# LM_001.net
KiCad netlist of a schematic drawn in Altium Designer
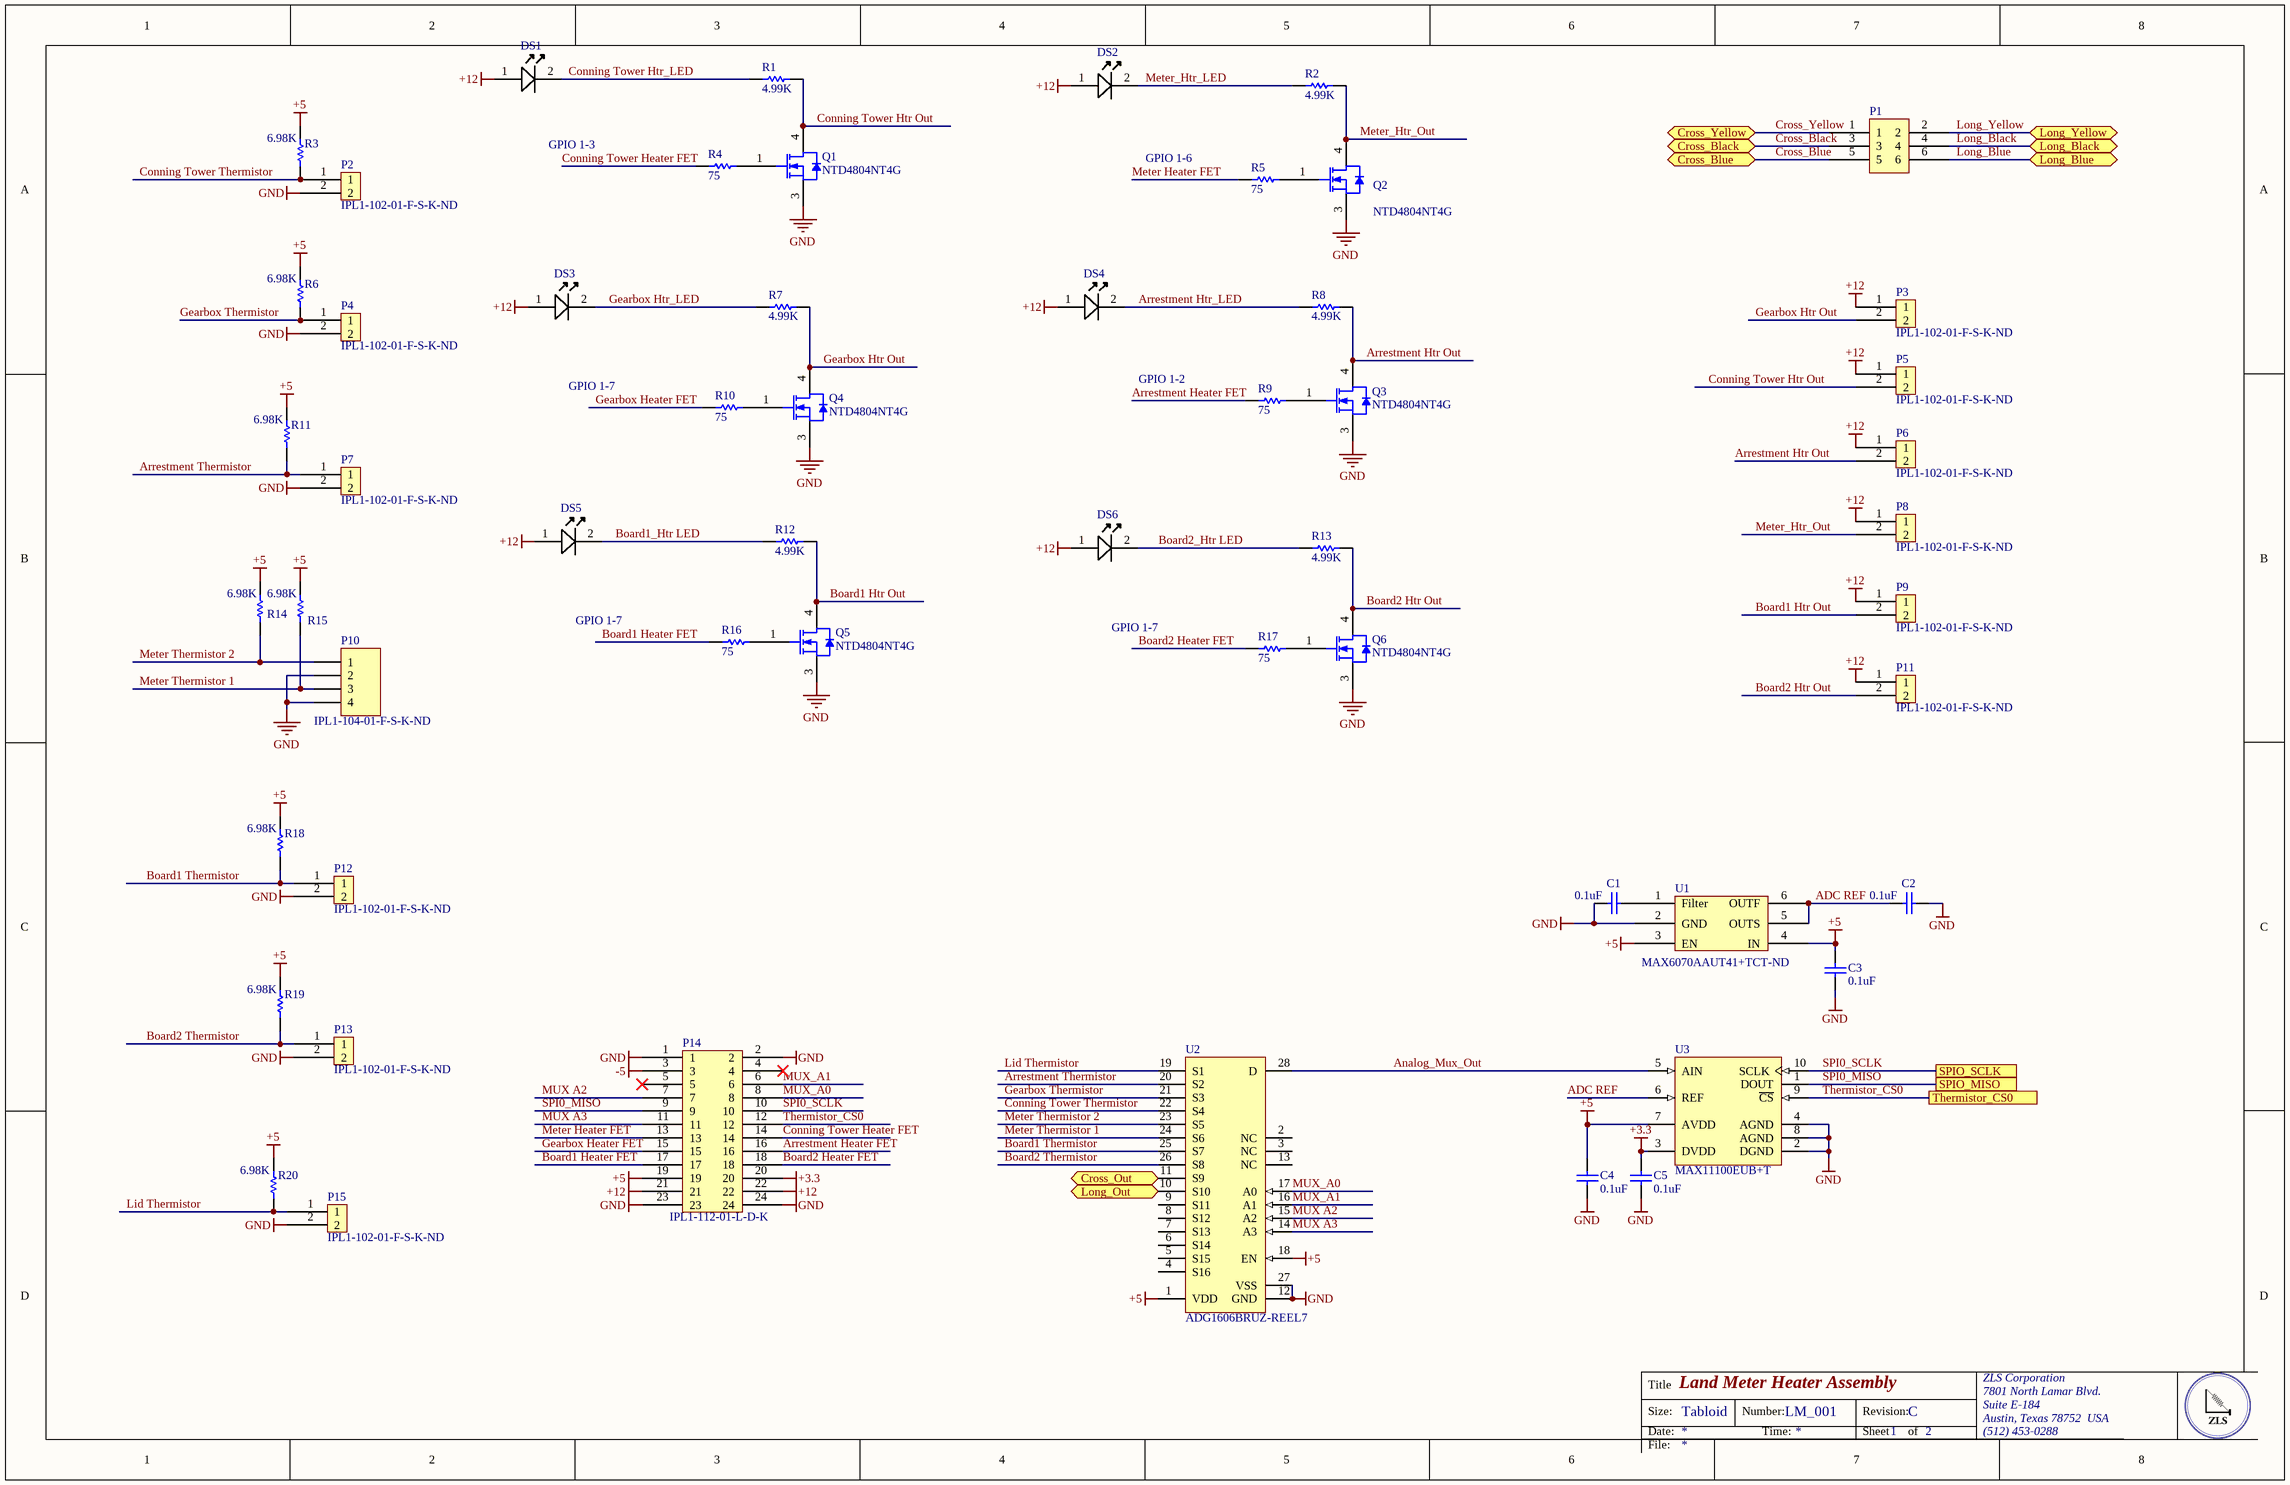
[diagram p0: LM_001.SchDoc]

(export (version "E")
  (design (tool "Eeschema 10.0.6"))
  (components
    (comp (ref "C1")
      (value "0.1uF")
      (footprint "CAPC0402(1005)60_L")
      (description "CAP CER 0.1UF 10V X7R 0402")
      (fields
        (field (name "MANUFACTURER") "Murata Electronics North America")
        (field (name "MANUFACTURER PART NUMBER") "GRM155R71A104KA01D")
      )
      (libsource (lib "Altium Content Vault") (part "CMP-1034-00252-1"))
    )
    (comp (ref "C2")
      (value "0.1uF")
      (footprint "CAPC0402(1005)60_L")
      (description "CAP CER 0.1UF 10V X7R 0402")
      (fields
        (field (name "MANUFACTURER") "Murata Electronics North America")
        (field (name "MANUFACTURER PART NUMBER") "GRM155R71A104KA01D")
      )
      (libsource (lib "Altium Content Vault") (part "CMP-1034-00252-1"))
    )
    (comp (ref "C3")
      (value "0.1uF")
      (footprint "CAPC0402(1005)60_L")
      (description "CAP CER 0.1UF 10V X7R 0402")
      (fields
        (field (name "MANUFACTURER") "Murata Electronics North America")
        (field (name "MANUFACTURER PART NUMBER") "GRM155R71A104KA01D")
      )
      (libsource (lib "Altium Content Vault") (part "CMP-1034-00252-1"))
    )
    (comp (ref "C4")
      (value "0.1uF")
      (footprint "CAPC0402(1005)60_L")
      (description "CAP CER 0.1UF 10V X7R 0402")
      (fields
        (field (name "MANUFACTURER") "Murata Electronics North America")
        (field (name "MANUFACTURER PART NUMBER") "GRM155R71A104KA01D")
      )
      (libsource (lib "Altium Content Vault") (part "CMP-1034-00252-1"))
    )
    (comp (ref "C5")
      (value "0.1uF")
      (footprint "CAPC0402(1005)60_L")
      (description "CAP CER 0.1UF 10V X7R 0402")
      (fields
        (field (name "MANUFACTURER") "Murata Electronics North America")
        (field (name "MANUFACTURER PART NUMBER") "GRM155R71A104KA01D")
      )
      (libsource (lib "Altium Content Vault") (part "CMP-1034-00252-1"))
    )
    (comp (ref "DS1")
      (value "LTST-S220KRKT")
      (footprint "0805C_L")
      (description "LED RED CLEAR CHIP SMD R/A")
      (fields (field (name "MANUFACTURER") "Vishay / Lite-On"))
      (libsource (lib "*") (part "LED A/K"))
    )
    (comp (ref "DS2")
      (value "LTST-S220KRKT")
      (footprint "0805C_L")
      (description "LED RED CLEAR CHIP SMD R/A")
      (fields (field (name "MANUFACTURER") "Vishay / Lite-On"))
      (libsource (lib "*") (part "LED A/K"))
    )
    (comp (ref "DS3")
      (value "LTST-S220KRKT")
      (footprint "0805C_L")
      (description "LED RED CLEAR CHIP SMD R/A")
      (fields (field (name "MANUFACTURER") "Vishay / Lite-On"))
      (libsource (lib "*") (part "LED A/K"))
    )
    (comp (ref "DS4")
      (value "LTST-S220KRKT")
      (footprint "0805C_L")
      (description "LED RED CLEAR CHIP SMD R/A")
      (fields (field (name "MANUFACTURER") "Vishay / Lite-On"))
      (libsource (lib "*") (part "LED A/K"))
    )
    (comp (ref "DS5")
      (value "LTST-S220KRKT")
      (footprint "0805C_L")
      (description "LED RED CLEAR CHIP SMD R/A")
      (fields (field (name "MANUFACTURER") "Vishay / Lite-On"))
      (libsource (lib "*") (part "LED A/K"))
    )
    (comp (ref "DS6")
      (value "LTST-S220KRKT")
      (footprint "0805C_L")
      (description "LED RED CLEAR CHIP SMD R/A")
      (fields (field (name "MANUFACTURER") "Vishay / Lite-On"))
      (libsource (lib "*") (part "LED A/K"))
    )
    (comp (ref "P1")
      (value "IPL1-103-01-L-D-K")
      (footprint "IPL1-103-01-F-D")
      (description ".100 TERMINAL ASSY")
      (fields (field (name "MANUFACTURER") "Samtec Inc."))
      (libsource (lib "ZLS_Schematic_lib") (part "IPL1-103-01-F-D"))
    )
    (comp (ref "P2")
      (value "IPL1-102-01-F-S-K")
      (footprint "IPL1-102-01-F-S-K")
      (description ".100 TERMINAL ASSEMBLY")
      (fields
        (field (name "SUPPLIER PART NUMBER 1") "IPL1-102-01-F-S-K-ND")
        (field (name "MANUFACTURER") "Samtec Inc.")
      )
      (libsource (lib "ZLS_Schematic_lib") (part "IPL1-102-01-F-S-K"))
    )
    (comp (ref "P3")
      (value "IPL1-102-01-F-S-K")
      (footprint "IPL1-102-01-F-S-K")
      (description ".100 TERMINAL ASSEMBLY")
      (fields
        (field (name "SUPPLIER PART NUMBER 1") "IPL1-102-01-F-S-K-ND")
        (field (name "MANUFACTURER") "Samtec Inc.")
      )
      (libsource (lib "ZLS_Schematic_lib") (part "IPL1-102-01-F-S-K"))
    )
    (comp (ref "P4")
      (value "IPL1-102-01-F-S-K")
      (footprint "IPL1-102-01-F-S-K")
      (description ".100 TERMINAL ASSEMBLY")
      (fields
        (field (name "SUPPLIER PART NUMBER 1") "IPL1-102-01-F-S-K-ND")
        (field (name "MANUFACTURER") "Samtec Inc.")
      )
      (libsource (lib "ZLS_Schematic_lib") (part "IPL1-102-01-F-S-K"))
    )
    (comp (ref "P5")
      (value "IPL1-102-01-F-S-K")
      (footprint "IPL1-102-01-F-S-K")
      (description ".100 TERMINAL ASSEMBLY")
      (fields
        (field (name "SUPPLIER PART NUMBER 1") "IPL1-102-01-F-S-K-ND")
        (field (name "MANUFACTURER") "Samtec Inc.")
      )
      (libsource (lib "ZLS_Schematic_lib") (part "IPL1-102-01-F-S-K"))
    )
    (comp (ref "P6")
      (value "IPL1-102-01-F-S-K")
      (footprint "IPL1-102-01-F-S-K")
      (description ".100 TERMINAL ASSEMBLY")
      (fields
        (field (name "SUPPLIER PART NUMBER 1") "IPL1-102-01-F-S-K-ND")
        (field (name "MANUFACTURER") "Samtec Inc.")
      )
      (libsource (lib "ZLS_Schematic_lib") (part "IPL1-102-01-F-S-K"))
    )
    (comp (ref "P7")
      (value "IPL1-102-01-F-S-K")
      (footprint "IPL1-102-01-F-S-K")
      (description ".100 TERMINAL ASSEMBLY")
      (fields
        (field (name "SUPPLIER PART NUMBER 1") "IPL1-102-01-F-S-K-ND")
        (field (name "MANUFACTURER") "Samtec Inc.")
      )
      (libsource (lib "ZLS_Schematic_lib") (part "IPL1-102-01-F-S-K"))
    )
    (comp (ref "P8")
      (value "IPL1-102-01-F-S-K")
      (footprint "IPL1-102-01-F-S-K")
      (description ".100 TERMINAL ASSEMBLY")
      (fields
        (field (name "SUPPLIER PART NUMBER 1") "IPL1-102-01-F-S-K-ND")
        (field (name "MANUFACTURER") "Samtec Inc.")
      )
      (libsource (lib "ZLS_Schematic_lib") (part "IPL1-102-01-F-S-K"))
    )
    (comp (ref "P9")
      (value "IPL1-102-01-F-S-K")
      (footprint "IPL1-102-01-F-S-K")
      (description ".100 TERMINAL ASSEMBLY")
      (fields
        (field (name "SUPPLIER PART NUMBER 1") "IPL1-102-01-F-S-K-ND")
        (field (name "MANUFACTURER") "Samtec Inc.")
      )
      (libsource (lib "ZLS_Schematic_lib") (part "IPL1-102-01-F-S-K"))
    )
    (comp (ref "P10")
      (value "IPL1-104-01-F-S-K-ND")
      (footprint "IPL1-104-01-L-S-K")
      (description ".100 TERMINAL ASSEMBLY")
      (fields
        (field (name "MANUFACTURER") "Samtec Inc.")
        (field (name "MANUFACTURER PART NUMBER") "IPL1-104-01-F-S-K")
      )
      (libsource (lib "Miscellaneous Connectors") (part "Header 4"))
    )
    (comp (ref "P11")
      (value "IPL1-102-01-F-S-K")
      (footprint "IPL1-102-01-F-S-K")
      (description ".100 TERMINAL ASSEMBLY")
      (fields
        (field (name "SUPPLIER PART NUMBER 1") "IPL1-102-01-F-S-K-ND")
        (field (name "MANUFACTURER") "Samtec Inc.")
      )
      (libsource (lib "ZLS_Schematic_lib") (part "IPL1-102-01-F-S-K"))
    )
    (comp (ref "P12")
      (value "IPL1-102-01-F-S-K")
      (footprint "IPL1-102-01-F-S-K")
      (description ".100 TERMINAL ASSEMBLY")
      (fields
        (field (name "SUPPLIER PART NUMBER 1") "IPL1-102-01-F-S-K-ND")
        (field (name "MANUFACTURER") "Samtec Inc.")
      )
      (libsource (lib "ZLS_Schematic_lib") (part "IPL1-102-01-F-S-K"))
    )
    (comp (ref "P13")
      (value "IPL1-102-01-F-S-K")
      (footprint "IPL1-102-01-F-S-K")
      (description ".100 TERMINAL ASSEMBLY")
      (fields
        (field (name "SUPPLIER PART NUMBER 1") "IPL1-102-01-F-S-K-ND")
        (field (name "MANUFACTURER") "Samtec Inc.")
      )
      (libsource (lib "ZLS_Schematic_lib") (part "IPL1-102-01-F-S-K"))
    )
    (comp (ref "P14")
      (value "IPL1-112-01-L-D-K")
      (footprint "IPL1-112-01-F-S-K")
      (description ".100 TERMINAL ASSEMBLY")
      (fields (field (name "MANUFACTURER") "Samtec Inc."))
      (libsource (lib "ZLS_Schematic_lib") (part "IPL1-112-01-F-S-K"))
    )
    (comp (ref "P15")
      (value "IPL1-102-01-F-S-K")
      (footprint "IPL1-102-01-F-S-K")
      (description ".100 TERMINAL ASSEMBLY")
      (fields
        (field (name "SUPPLIER PART NUMBER 1") "IPL1-102-01-F-S-K-ND")
        (field (name "MANUFACTURER") "Samtec Inc.")
      )
      (libsource (lib "ZLS_Schematic_lib") (part "IPL1-102-01-F-S-K"))
    )
    (comp (ref "Q1")
      (value "NTD4804NT4G")
      (footprint "ONSC-DPAK-3-369AA-01_V")
      (description "Power MOSFET, 30 V, 117 A, Single N-Channel, 3-Pin DPAK, Pb-Free, Tape and Reel")
      (fields (field (name "MANUFACTURER") "On Semiconductor"))
      (libsource (lib "Altium Content Vault") (part "CMP-1058-00341-1"))
    )
    (comp (ref "Q2")
      (value "NTD4804NT4G")
      (footprint "ONSC-DPAK-3-369AA-01_V")
      (description "Power MOSFET, 30 V, 117 A, Single N-Channel, 3-Pin DPAK, Pb-Free, Tape and Reel")
      (fields (field (name "MANUFACTURER") "On Semiconductor"))
      (libsource (lib "Altium Content Vault") (part "CMP-1058-00341-1"))
    )
    (comp (ref "Q3")
      (value "NTD4804NT4G")
      (footprint "ONSC-DPAK-3-369AA-01_V")
      (description "Power MOSFET, 30 V, 117 A, Single N-Channel, 3-Pin DPAK, Pb-Free, Tape and Reel")
      (fields (field (name "MANUFACTURER") "On Semiconductor"))
      (libsource (lib "Altium Content Vault") (part "CMP-1058-00341-1"))
    )
    (comp (ref "Q4")
      (value "NTD4804NT4G")
      (footprint "ONSC-DPAK-3-369AA-01_V")
      (description "Power MOSFET, 30 V, 117 A, Single N-Channel, 3-Pin DPAK, Pb-Free, Tape and Reel")
      (fields (field (name "MANUFACTURER") "On Semiconductor"))
      (libsource (lib "Altium Content Vault") (part "CMP-1058-00341-1"))
    )
    (comp (ref "Q5")
      (value "NTD4804NT4G")
      (footprint "ONSC-DPAK-3-369AA-01_V")
      (description "Power MOSFET, 30 V, 117 A, Single N-Channel, 3-Pin DPAK, Pb-Free, Tape and Reel")
      (fields (field (name "MANUFACTURER") "On Semiconductor"))
      (libsource (lib "Altium Content Vault") (part "CMP-1058-00341-1"))
    )
    (comp (ref "Q6")
      (value "NTD4804NT4G")
      (footprint "ONSC-DPAK-3-369AA-01_V")
      (description "Power MOSFET, 30 V, 117 A, Single N-Channel, 3-Pin DPAK, Pb-Free, Tape and Reel")
      (fields (field (name "MANUFACTURER") "On Semiconductor"))
      (libsource (lib "Altium Content Vault") (part "CMP-1058-00341-1"))
    )
    (comp (ref "R1")
      (value "4.99K")
      (footprint "RESC0805(2012)_L")
      (description "RES SMD 4.99K OHM 1% 1/8W 0805")
      (fields
        (field (name "MANUFACTURER") "Vishay Dale")
        (field (name "MANUFACTURER PART NUMBER") "CRCW08054K99FKEA")
      )
      (libsource (lib "Altium Content Vault") (part "CMP-1013-00393-1"))
    )
    (comp (ref "R2")
      (value "4.99K")
      (footprint "RESC0805(2012)_L")
      (description "RES SMD 4.99K OHM 1% 1/8W 0805")
      (fields
        (field (name "MANUFACTURER") "Vishay Dale")
        (field (name "MANUFACTURER PART NUMBER") "CRCW08054K99FKEA")
      )
      (libsource (lib "Altium Content Vault") (part "CMP-1013-00393-1"))
    )
    (comp (ref "R3")
      (value "6.98K")
      (footprint "RESC0805(2012)_N")
      (description "RES SMD 6.98K OHM 1% 1/8W 0805")
      (fields
        (field (name "MANUFACTURER") "Vishay Dale")
        (field (name "MANUFACTURER PART NUMBER") "CRCW08056K98FKEA")
      )
      (libsource (lib "Altium Content Vault") (part "CMP-1013-00606-1"))
    )
    (comp (ref "R4")
      (value "75")
      (footprint "RESC0805(2012)_L")
      (description "RES SMD 75 OHM 1% 1/8W 0805")
      (fields
        (field (name "MANUFACTURER") "Vishay Dale")
        (field (name "MANUFACTURER PART NUMBER") "CRCW080575R0FKTA")
      )
      (libsource (lib "Altium Content Vault") (part "CMP-1013-00393-1"))
    )
    (comp (ref "R5")
      (value "75")
      (footprint "RESC0805(2012)_L")
      (description "RES SMD 75 OHM 1% 1/8W 0805")
      (fields
        (field (name "MANUFACTURER") "Vishay Dale")
        (field (name "MANUFACTURER PART NUMBER") "CRCW080575R0FKTA")
      )
      (libsource (lib "Altium Content Vault") (part "CMP-1013-00393-1"))
    )
    (comp (ref "R6")
      (value "6.98K")
      (footprint "RESC0805(2012)_N")
      (description "RES SMD 6.98K OHM 1% 1/8W 0805")
      (fields
        (field (name "MANUFACTURER") "Vishay Dale")
        (field (name "MANUFACTURER PART NUMBER") "CRCW08056K98FKEA")
      )
      (libsource (lib "Altium Content Vault") (part "CMP-1013-00606-1"))
    )
    (comp (ref "R7")
      (value "4.99K")
      (footprint "RESC0805(2012)_L")
      (description "RES SMD 4.99K OHM 1% 1/8W 0805")
      (fields
        (field (name "MANUFACTURER") "Vishay Dale")
        (field (name "MANUFACTURER PART NUMBER") "CRCW08054K99FKEA")
      )
      (libsource (lib "Altium Content Vault") (part "CMP-1013-00393-1"))
    )
    (comp (ref "R8")
      (value "4.99K")
      (footprint "RESC0805(2012)_L")
      (description "RES SMD 4.99K OHM 1% 1/8W 0805")
      (fields
        (field (name "MANUFACTURER") "Vishay Dale")
        (field (name "MANUFACTURER PART NUMBER") "CRCW08054K99FKEA")
      )
      (libsource (lib "Altium Content Vault") (part "CMP-1013-00393-1"))
    )
    (comp (ref "R9")
      (value "75")
      (footprint "RESC0805(2012)_L")
      (description "RES SMD 75 OHM 1% 1/8W 0805")
      (fields
        (field (name "MANUFACTURER") "Vishay Dale")
        (field (name "MANUFACTURER PART NUMBER") "CRCW080575R0FKTA")
      )
      (libsource (lib "Altium Content Vault") (part "CMP-1013-00393-1"))
    )
    (comp (ref "R10")
      (value "75")
      (footprint "RESC0805(2012)_L")
      (description "RES SMD 75 OHM 1% 1/8W 0805")
      (fields
        (field (name "MANUFACTURER") "Vishay Dale")
        (field (name "MANUFACTURER PART NUMBER") "CRCW080575R0FKTA")
      )
      (libsource (lib "Altium Content Vault") (part "CMP-1013-00393-1"))
    )
    (comp (ref "R11")
      (value "6.98K")
      (footprint "RESC0805(2012)_N")
      (description "RES SMD 6.98K OHM 1% 1/8W 0805")
      (fields
        (field (name "MANUFACTURER") "Vishay Dale")
        (field (name "MANUFACTURER PART NUMBER") "CRCW08056K98FKEA")
      )
      (libsource (lib "Altium Content Vault") (part "CMP-1013-00606-1"))
    )
    (comp (ref "R12")
      (value "4.99K")
      (footprint "RESC0805(2012)_L")
      (description "RES SMD 4.99K OHM 1% 1/8W 0805")
      (fields
        (field (name "MANUFACTURER") "Vishay Dale")
        (field (name "MANUFACTURER PART NUMBER") "CRCW08054K99FKEA")
      )
      (libsource (lib "Altium Content Vault") (part "CMP-1013-00393-1"))
    )
    (comp (ref "R13")
      (value "4.99K")
      (footprint "RESC0805(2012)_L")
      (description "RES SMD 4.99K OHM 1% 1/8W 0805")
      (fields
        (field (name "MANUFACTURER") "Vishay Dale")
        (field (name "MANUFACTURER PART NUMBER") "CRCW08054K99FKEA")
      )
      (libsource (lib "Altium Content Vault") (part "CMP-1013-00393-1"))
    )
    (comp (ref "R14")
      (value "6.98K")
      (footprint "RESC0805(2012)_N")
      (description "RES SMD 6.98K OHM 1% 1/8W 0805")
      (fields
        (field (name "MANUFACTURER") "Vishay Dale")
        (field (name "MANUFACTURER PART NUMBER") "CRCW08056K98FKEA")
      )
      (libsource (lib "Altium Content Vault") (part "CMP-1013-00606-1"))
    )
    (comp (ref "R15")
      (value "6.98K")
      (footprint "RESC0805(2012)_N")
      (description "RES SMD 6.98K OHM 1% 1/8W 0805")
      (fields
        (field (name "MANUFACTURER") "Vishay Dale")
        (field (name "MANUFACTURER PART NUMBER") "CRCW08056K98FKEA")
      )
      (libsource (lib "Altium Content Vault") (part "CMP-1013-00606-1"))
    )
    (comp (ref "R16")
      (value "75")
      (footprint "RESC0805(2012)_L")
      (description "RES SMD 75 OHM 1% 1/8W 0805")
      (fields
        (field (name "MANUFACTURER") "Vishay Dale")
        (field (name "MANUFACTURER PART NUMBER") "CRCW080575R0FKTA")
      )
      (libsource (lib "Altium Content Vault") (part "CMP-1013-00393-1"))
    )
    (comp (ref "R17")
      (value "75")
      (footprint "RESC0805(2012)_L")
      (description "RES SMD 75 OHM 1% 1/8W 0805")
      (fields
        (field (name "MANUFACTURER") "Vishay Dale")
        (field (name "MANUFACTURER PART NUMBER") "CRCW080575R0FKTA")
      )
      (libsource (lib "Altium Content Vault") (part "CMP-1013-00393-1"))
    )
    (comp (ref "R18")
      (value "6.98K")
      (footprint "RESC0805(2012)_N")
      (description "RES SMD 6.98K OHM 1% 1/8W 0805")
      (fields
        (field (name "MANUFACTURER") "Vishay Dale")
        (field (name "MANUFACTURER PART NUMBER") "CRCW08056K98FKEA")
      )
      (libsource (lib "Altium Content Vault") (part "CMP-1013-00606-1"))
    )
    (comp (ref "R19")
      (value "6.98K")
      (footprint "RESC0805(2012)_N")
      (description "RES SMD 6.98K OHM 1% 1/8W 0805")
      (fields
        (field (name "MANUFACTURER") "Vishay Dale")
        (field (name "MANUFACTURER PART NUMBER") "CRCW08056K98FKEA")
      )
      (libsource (lib "Altium Content Vault") (part "CMP-1013-00606-1"))
    )
    (comp (ref "R20")
      (value "6.98K")
      (footprint "RESC0805(2012)_N")
      (description "RES SMD 6.98K OHM 1% 1/8W 0805")
      (fields
        (field (name "MANUFACTURER") "Vishay Dale")
        (field (name "MANUFACTURER PART NUMBER") "CRCW08056K98FKEA")
      )
      (libsource (lib "Altium Content Vault") (part "CMP-1013-00606-1"))
    )
    (comp (ref "U1")
      (value "MAX6070AAUT41+T")
      (footprint "SOT95P280X445-6N")
      (description "IC VREF SERIES 4.096V SOT23")
      (fields
        (field (name "SUPPLIER PART NUMBER 1") "MAX6070AAUT41+TCT-ND")
        (field (name "MANUFACTURER") "Maxim Integrated")
        (field (name "TOLERANCE") "±0.04%")
      )
      (libsource (lib "ZLS_Schematic_lib") (part "MAX6070AAUT41+T"))
    )
    (comp (ref "U2")
      (value "ADG1606BRUZ-REEL7")
      (footprint "ADI-RU-28_M")
      (description "4.5 Ohm Ron, 16-Channel, +/-5 V,+12 V,+5 V and +3.3 V Multiplexer, 28-pin SOP (RU-28), Reel")
      (fields (field (name "MANUFACTURER") "Analog Devices"))
      (libsource (lib "Altium Content Vault") (part "ADI-ADG1606-RU-28"))
    )
    (comp (ref "U3")
      (value "MAX11100EUB+T")
      (footprint "U10+2_L")
      (description "16-Bit, +5V, 200ksps ADC with 10uA Shutdown, 10-Pin uMAX, -40°C to +85°C, Pb-Free, Tape and Reel")
      (libsource (lib "Altium Content Vault") (part "CON-ADC-MAX11100-IL10"))
    )
  )
  (nets
    (net (code "1") (name "+3.3") (class "Default")
      (node (ref "C5") (pin "1") (pinfunction "1_1") (pintype "passive"))
      (node (ref "P14") (pin "20") (pinfunction "20_20") (pintype "passive"))
      (node (ref "U3") (pin "3") (pinfunction "DVDD_3") (pintype "power_in"))
    )
    (net (code "2") (name "+5") (class "Default")
      (node (ref "C3") (pin "1") (pinfunction "1_1") (pintype "passive"))
      (node (ref "C4") (pin "1") (pinfunction "1_1") (pintype "passive"))
      (node (ref "P14") (pin "19") (pinfunction "19_19") (pintype "passive"))
      (node (ref "R11") (pin "2") (pinfunction "2_2") (pintype "passive"))
      (node (ref "R14") (pin "2") (pinfunction "2_2") (pintype "passive"))
      (node (ref "R15") (pin "2") (pinfunction "2_2") (pintype "passive"))
      (node (ref "R18") (pin "2") (pinfunction "2_2") (pintype "passive"))
      (node (ref "R19") (pin "2") (pinfunction "2_2") (pintype "passive"))
      (node (ref "R20") (pin "2") (pinfunction "2_2") (pintype "passive"))
      (node (ref "R3") (pin "2") (pinfunction "2_2") (pintype "passive"))
      (node (ref "R6") (pin "2") (pinfunction "2_2") (pintype "passive"))
      (node (ref "U1") (pin "3") (pinfunction "EN_3") (pintype "passive"))
      (node (ref "U1") (pin "4") (pinfunction "IN_4") (pintype "passive"))
      (node (ref "U2") (pin "1") (pinfunction "VDD_1") (pintype "power_in"))
      (node (ref "U2") (pin "18") (pinfunction "EN_18") (pintype "input"))
      (node (ref "U3") (pin "7") (pinfunction "AVDD_7") (pintype "power_in"))
    )
    (net (code "3") (name "+12") (class "Default")
      (node (ref "DS1") (pin "1") (pinfunction "A_1") (pintype "passive"))
      (node (ref "DS2") (pin "1") (pinfunction "A_1") (pintype "passive"))
      (node (ref "DS3") (pin "1") (pinfunction "A_1") (pintype "passive"))
      (node (ref "DS4") (pin "1") (pinfunction "A_1") (pintype "passive"))
      (node (ref "DS5") (pin "1") (pinfunction "A_1") (pintype "passive"))
      (node (ref "DS6") (pin "1") (pinfunction "A_1") (pintype "passive"))
      (node (ref "P11") (pin "1") (pinfunction "1_1") (pintype "passive"))
      (node (ref "P14") (pin "21") (pinfunction "21_21") (pintype "passive"))
      (node (ref "P14") (pin "22") (pinfunction "22_22") (pintype "passive"))
      (node (ref "P3") (pin "1") (pinfunction "1_1") (pintype "passive"))
      (node (ref "P5") (pin "1") (pinfunction "1_1") (pintype "passive"))
      (node (ref "P6") (pin "1") (pinfunction "1_1") (pintype "passive"))
      (node (ref "P8") (pin "1") (pinfunction "1_1") (pintype "passive"))
      (node (ref "P9") (pin "1") (pinfunction "1_1") (pintype "passive"))
    )
    (net (code "4") (name "-5") (class "Default")
      (node (ref "P14") (pin "3") (pinfunction "3_3") (pintype "passive"))
    )
    (net (code "5") (name "/ADC REF") (class "Default")
      (node (ref "C2") (pin "2") (pinfunction "2_2") (pintype "passive"))
      (node (ref "U1") (pin "5") (pinfunction "OUTS_5") (pintype "passive"))
      (node (ref "U1") (pin "6") (pinfunction "OUTF_6") (pintype "passive"))
      (node (ref "U3") (pin "6") (pinfunction "REF_6") (pintype "input"))
    )
    (net (code "6") (name "/Analog_Mux_Out") (class "Default")
      (node (ref "U2") (pin "28") (pinfunction "D_28") (pintype "passive"))
      (node (ref "U3") (pin "5") (pinfunction "AIN_5") (pintype "input"))
    )
    (net (code "7") (name "/Arrestment Heater FET") (class "Default")
      (node (ref "P14") (pin "16") (pinfunction "16_16") (pintype "passive"))
      (node (ref "R9") (pin "1") (pinfunction "1_1") (pintype "passive"))
    )
    (net (code "8") (name "/Arrestment Htr Out") (class "Default")
      (node (ref "P6") (pin "2") (pinfunction "2_2") (pintype "passive"))
      (node (ref "Q3") (pin "4") (pinfunction "D_4") (pintype "passive"))
      (node (ref "R8") (pin "1") (pinfunction "1_1") (pintype "passive"))
    )
    (net (code "9") (name "/Arrestment Htr_LED") (class "Default")
      (node (ref "DS4") (pin "2") (pinfunction "K_2") (pintype "passive"))
      (node (ref "R8") (pin "2") (pinfunction "2_2") (pintype "passive"))
    )
    (net (code "10") (name "/Arrestment Thermistor") (class "Default")
      (node (ref "P7") (pin "1") (pinfunction "1_1") (pintype "passive"))
      (node (ref "R11") (pin "1") (pinfunction "1_1") (pintype "passive"))
      (node (ref "U2") (pin "20") (pinfunction "S2_20") (pintype "passive"))
    )
    (net (code "11") (name "/Board1 Heater FET") (class "Default")
      (node (ref "P14") (pin "17") (pinfunction "17_17") (pintype "passive"))
      (node (ref "R16") (pin "1") (pinfunction "1_1") (pintype "passive"))
    )
    (net (code "12") (name "/Board1 Htr Out") (class "Default")
      (node (ref "P9") (pin "2") (pinfunction "2_2") (pintype "passive"))
      (node (ref "Q5") (pin "4") (pinfunction "D_4") (pintype "passive"))
      (node (ref "R12") (pin "1") (pinfunction "1_1") (pintype "passive"))
    )
    (net (code "13") (name "/Board1 Thermistor") (class "Default")
      (node (ref "P12") (pin "1") (pinfunction "1_1") (pintype "passive"))
      (node (ref "R18") (pin "1") (pinfunction "1_1") (pintype "passive"))
      (node (ref "U2") (pin "25") (pinfunction "S7_25") (pintype "passive"))
    )
    (net (code "14") (name "/Board1_Htr LED") (class "Default")
      (node (ref "DS5") (pin "2") (pinfunction "K_2") (pintype "passive"))
      (node (ref "R12") (pin "2") (pinfunction "2_2") (pintype "passive"))
    )
    (net (code "15") (name "/Board2 Heater FET") (class "Default")
      (node (ref "P14") (pin "18") (pinfunction "18_18") (pintype "passive"))
      (node (ref "R17") (pin "1") (pinfunction "1_1") (pintype "passive"))
    )
    (net (code "16") (name "/Board2 Htr Out") (class "Default")
      (node (ref "P11") (pin "2") (pinfunction "2_2") (pintype "passive"))
      (node (ref "Q6") (pin "4") (pinfunction "D_4") (pintype "passive"))
      (node (ref "R13") (pin "1") (pinfunction "1_1") (pintype "passive"))
    )
    (net (code "17") (name "/Board2 Thermistor") (class "Default")
      (node (ref "P13") (pin "1") (pinfunction "1_1") (pintype "passive"))
      (node (ref "R19") (pin "1") (pinfunction "1_1") (pintype "passive"))
      (node (ref "U2") (pin "26") (pinfunction "S8_26") (pintype "passive"))
    )
    (net (code "18") (name "/Board2_Htr LED") (class "Default")
      (node (ref "DS6") (pin "2") (pinfunction "K_2") (pintype "passive"))
      (node (ref "R13") (pin "2") (pinfunction "2_2") (pintype "passive"))
    )
    (net (code "19") (name "/Conning Tower Heater FET") (class "Default")
      (node (ref "P14") (pin "14") (pinfunction "14_14") (pintype "passive"))
      (node (ref "R4") (pin "1") (pinfunction "1_1") (pintype "passive"))
    )
    (net (code "20") (name "/Conning Tower Htr Out") (class "Default")
      (node (ref "P5") (pin "2") (pinfunction "2_2") (pintype "passive"))
      (node (ref "Q1") (pin "4") (pinfunction "D_4") (pintype "passive"))
      (node (ref "R1") (pin "1") (pinfunction "1_1") (pintype "passive"))
    )
    (net (code "21") (name "/Conning Tower Htr_LED") (class "Default")
      (node (ref "DS1") (pin "2") (pinfunction "K_2") (pintype "passive"))
      (node (ref "R1") (pin "2") (pinfunction "2_2") (pintype "passive"))
    )
    (net (code "22") (name "/Conning Tower Thermistor") (class "Default")
      (node (ref "P2") (pin "1") (pinfunction "1_1") (pintype "passive"))
      (node (ref "R3") (pin "1") (pinfunction "1_1") (pintype "passive"))
      (node (ref "U2") (pin "22") (pinfunction "S4_22") (pintype "passive"))
    )
    (net (code "23") (name "/Cross_Black") (class "Default")
      (node (ref "P1") (pin "3") (pinfunction "3_3") (pintype "passive"))
    )
    (net (code "24") (name "/Cross_Blue") (class "Default")
      (node (ref "P1") (pin "5") (pinfunction "5_5") (pintype "passive"))
    )
    (net (code "25") (name "/Cross_Out") (class "Default")
      (node (ref "U2") (pin "11") (pinfunction "S9_11") (pintype "passive"))
    )
    (net (code "26") (name "/Cross_Yellow") (class "Default")
      (node (ref "P1") (pin "1") (pinfunction "1_1") (pintype "passive"))
    )
    (net (code "27") (name "/Gearbox Heater FET") (class "Default")
      (node (ref "P14") (pin "15") (pinfunction "15_15") (pintype "passive"))
      (node (ref "R10") (pin "1") (pinfunction "1_1") (pintype "passive"))
    )
    (net (code "28") (name "/Gearbox Htr Out") (class "Default")
      (node (ref "P3") (pin "2") (pinfunction "2_2") (pintype "passive"))
      (node (ref "Q4") (pin "4") (pinfunction "D_4") (pintype "passive"))
      (node (ref "R7") (pin "1") (pinfunction "1_1") (pintype "passive"))
    )
    (net (code "29") (name "/Gearbox Htr_LED") (class "Default")
      (node (ref "DS3") (pin "2") (pinfunction "K_2") (pintype "passive"))
      (node (ref "R7") (pin "2") (pinfunction "2_2") (pintype "passive"))
    )
    (net (code "30") (name "/Gearbox Thermistor") (class "Default")
      (node (ref "P4") (pin "1") (pinfunction "1_1") (pintype "passive"))
      (node (ref "R6") (pin "1") (pinfunction "1_1") (pintype "passive"))
      (node (ref "U2") (pin "21") (pinfunction "S3_21") (pintype "passive"))
    )
    (net (code "31") (name "/Lid Thermistor") (class "Default")
      (node (ref "P15") (pin "1") (pinfunction "1_1") (pintype "passive"))
      (node (ref "R20") (pin "1") (pinfunction "1_1") (pintype "passive"))
      (node (ref "U2") (pin "19") (pinfunction "S1_19") (pintype "passive"))
    )
    (net (code "32") (name "/Long_Black") (class "Default")
      (node (ref "P1") (pin "4") (pinfunction "4_4") (pintype "passive"))
    )
    (net (code "33") (name "/Long_Blue") (class "Default")
      (node (ref "P1") (pin "6") (pinfunction "6_6") (pintype "passive"))
    )
    (net (code "34") (name "/Long_Out") (class "Default")
      (node (ref "U2") (pin "10") (pinfunction "S10_10") (pintype "passive"))
    )
    (net (code "35") (name "/Long_Yellow") (class "Default")
      (node (ref "P1") (pin "2") (pinfunction "2_2") (pintype "passive"))
    )
    (net (code "36") (name "/MUX A2") (class "Default")
      (node (ref "P14") (pin "7") (pinfunction "7_7") (pintype "passive"))
      (node (ref "U2") (pin "15") (pinfunction "A2_15") (pintype "input"))
    )
    (net (code "37") (name "/MUX A3") (class "Default")
      (node (ref "P14") (pin "11") (pinfunction "11_11") (pintype "passive"))
      (node (ref "U2") (pin "14") (pinfunction "A3_14") (pintype "input"))
    )
    (net (code "38") (name "/MUX_A0") (class "Default")
      (node (ref "P14") (pin "8") (pinfunction "8_8") (pintype "passive"))
      (node (ref "U2") (pin "17") (pinfunction "A0_17") (pintype "input"))
    )
    (net (code "39") (name "/MUX_A1") (class "Default")
      (node (ref "P14") (pin "6") (pinfunction "6_6") (pintype "passive"))
      (node (ref "U2") (pin "16") (pinfunction "A1_16") (pintype "input"))
    )
    (net (code "40") (name "/Meter Heater FET") (class "Default")
      (node (ref "P14") (pin "13") (pinfunction "13_13") (pintype "passive"))
      (node (ref "R5") (pin "1") (pinfunction "1_1") (pintype "passive"))
    )
    (net (code "41") (name "/Meter Thermistor 1") (class "Default")
      (node (ref "P10") (pin "3") (pinfunction "3_3") (pintype "passive"))
      (node (ref "R15") (pin "1") (pinfunction "1_1") (pintype "passive"))
      (node (ref "U2") (pin "24") (pinfunction "S6_24") (pintype "passive"))
    )
    (net (code "42") (name "/Meter Thermistor 2") (class "Default")
      (node (ref "P10") (pin "1") (pinfunction "1_1") (pintype "passive"))
      (node (ref "R14") (pin "1") (pinfunction "1_1") (pintype "passive"))
      (node (ref "U2") (pin "23") (pinfunction "S5_23") (pintype "passive"))
    )
    (net (code "43") (name "/Meter_Htr_LED") (class "Default")
      (node (ref "DS2") (pin "2") (pinfunction "K_2") (pintype "passive"))
      (node (ref "R2") (pin "2") (pinfunction "2_2") (pintype "passive"))
    )
    (net (code "44") (name "/Meter_Htr_Out") (class "Default")
      (node (ref "P8") (pin "2") (pinfunction "2_2") (pintype "passive"))
      (node (ref "Q2") (pin "4") (pinfunction "D_4") (pintype "passive"))
      (node (ref "R2") (pin "1") (pinfunction "1_1") (pintype "passive"))
    )
    (net (code "45") (name "/SPI0_MISO") (class "Default")
      (node (ref "P14") (pin "9") (pinfunction "9_9") (pintype "passive"))
      (node (ref "U3") (pin "1") (pinfunction "DOUT_1") (pintype "tri_state"))
    )
    (net (code "46") (name "/SPI0_SCLK") (class "Default")
      (node (ref "P14") (pin "10") (pinfunction "10_10") (pintype "passive"))
      (node (ref "U3") (pin "10") (pinfunction "SCLK_10") (pintype "input"))
    )
    (net (code "47") (name "/Thermistor_CS0") (class "Default")
      (node (ref "P14") (pin "12") (pinfunction "12_12") (pintype "passive"))
      (node (ref "U3") (pin "9") (pinfunction "~{CS}_9") (pintype "input"))
    )
    (net (code "48") (name "GND") (class "Default")
      (node (ref "C1") (pin "2") (pinfunction "2_2") (pintype "passive"))
      (node (ref "C2") (pin "1") (pinfunction "1_1") (pintype "passive"))
      (node (ref "C3") (pin "2") (pinfunction "2_2") (pintype "passive"))
      (node (ref "C4") (pin "2") (pinfunction "2_2") (pintype "passive"))
      (node (ref "C5") (pin "2") (pinfunction "2_2") (pintype "passive"))
      (node (ref "P10") (pin "2") (pinfunction "2_2") (pintype "passive"))
      (node (ref "P10") (pin "4") (pinfunction "4_4") (pintype "passive"))
      (node (ref "P12") (pin "2") (pinfunction "2_2") (pintype "passive"))
      (node (ref "P13") (pin "2") (pinfunction "2_2") (pintype "passive"))
      (node (ref "P14") (pin "1") (pinfunction "1_1") (pintype "passive"))
      (node (ref "P14") (pin "2") (pinfunction "2_2") (pintype "passive"))
      (node (ref "P14") (pin "23") (pinfunction "23_23") (pintype "passive"))
      (node (ref "P14") (pin "24") (pinfunction "24_24") (pintype "passive"))
      (node (ref "P15") (pin "2") (pinfunction "2_2") (pintype "passive"))
      (node (ref "P2") (pin "2") (pinfunction "2_2") (pintype "passive"))
      (node (ref "P4") (pin "2") (pinfunction "2_2") (pintype "passive"))
      (node (ref "P7") (pin "2") (pinfunction "2_2") (pintype "passive"))
      (node (ref "Q1") (pin "3") (pinfunction "S_3") (pintype "passive"))
      (node (ref "Q2") (pin "3") (pinfunction "S_3") (pintype "passive"))
      (node (ref "Q3") (pin "3") (pinfunction "S_3") (pintype "passive"))
      (node (ref "Q4") (pin "3") (pinfunction "S_3") (pintype "passive"))
      (node (ref "Q5") (pin "3") (pinfunction "S_3") (pintype "passive"))
      (node (ref "Q6") (pin "3") (pinfunction "S_3") (pintype "passive"))
      (node (ref "U1") (pin "2") (pinfunction "GND_2") (pintype "passive"))
      (node (ref "U2") (pin "12") (pinfunction "GND_12") (pintype "power_in"))
      (node (ref "U2") (pin "27") (pinfunction "VSS_27") (pintype "power_in"))
      (node (ref "U3") (pin "2") (pinfunction "DGND_2") (pintype "power_in"))
      (node (ref "U3") (pin "4") (pinfunction "AGND_4") (pintype "power_in"))
      (node (ref "U3") (pin "8") (pinfunction "AGND_8") (pintype "power_in"))
    )
    (net (code "49") (name "Net-(Q1-G)") (class "Default")
      (node (ref "Q1") (pin "1") (pinfunction "G_1") (pintype "passive"))
      (node (ref "R4") (pin "2") (pinfunction "2_2") (pintype "passive"))
    )
    (net (code "50") (name "Net-(Q2-G)") (class "Default")
      (node (ref "Q2") (pin "1") (pinfunction "G_1") (pintype "passive"))
      (node (ref "R5") (pin "2") (pinfunction "2_2") (pintype "passive"))
    )
    (net (code "51") (name "Net-(Q3-G)") (class "Default")
      (node (ref "Q3") (pin "1") (pinfunction "G_1") (pintype "passive"))
      (node (ref "R9") (pin "2") (pinfunction "2_2") (pintype "passive"))
    )
    (net (code "52") (name "Net-(Q4-G)") (class "Default")
      (node (ref "Q4") (pin "1") (pinfunction "G_1") (pintype "passive"))
      (node (ref "R10") (pin "2") (pinfunction "2_2") (pintype "passive"))
    )
    (net (code "53") (name "Net-(Q5-G)") (class "Default")
      (node (ref "Q5") (pin "1") (pinfunction "G_1") (pintype "passive"))
      (node (ref "R16") (pin "2") (pinfunction "2_2") (pintype "passive"))
    )
    (net (code "54") (name "Net-(Q6-G)") (class "Default")
      (node (ref "Q6") (pin "1") (pinfunction "G_1") (pintype "passive"))
      (node (ref "R17") (pin "2") (pinfunction "2_2") (pintype "passive"))
    )
    (net (code "55") (name "Net-(U1-Filter)") (class "Default")
      (node (ref "C1") (pin "1") (pinfunction "1_1") (pintype "passive"))
      (node (ref "U1") (pin "1") (pinfunction "Filter_1") (pintype "passive"))
    )
    (net (code "56") (name "unconnected-(P14-Pad4)") (class "Default")
      (node (ref "P14") (pin "4") (pinfunction "4_4") (pintype "passive+no_connect"))
    )
    (net (code "57") (name "unconnected-(P14-Pad5)") (class "Default")
      (node (ref "P14") (pin "5") (pinfunction "5_5") (pintype "passive+no_connect"))
    )
    (net (code "58") (name "unconnected-(U2-NC-Pad2)") (class "Default")
      (node (ref "U2") (pin "2") (pinfunction "NC_2") (pintype "passive"))
    )
    (net (code "59") (name "unconnected-(U2-NC-Pad3)") (class "Default")
      (node (ref "U2") (pin "3") (pinfunction "NC_3") (pintype "passive"))
    )
    (net (code "60") (name "unconnected-(U2-NC-Pad13)") (class "Default")
      (node (ref "U2") (pin "13") (pinfunction "NC_13") (pintype "passive"))
    )
    (net (code "61") (name "unconnected-(U2-S11-Pad9)") (class "Default")
      (node (ref "U2") (pin "9") (pinfunction "S11_9") (pintype "passive"))
    )
    (net (code "62") (name "unconnected-(U2-S12-Pad8)") (class "Default")
      (node (ref "U2") (pin "8") (pinfunction "S12_8") (pintype "passive"))
    )
    (net (code "63") (name "unconnected-(U2-S13-Pad7)") (class "Default")
      (node (ref "U2") (pin "7") (pinfunction "S13_7") (pintype "passive"))
    )
    (net (code "64") (name "unconnected-(U2-S14-Pad6)") (class "Default")
      (node (ref "U2") (pin "6") (pinfunction "S14_6") (pintype "passive"))
    )
    (net (code "65") (name "unconnected-(U2-S15-Pad5)") (class "Default")
      (node (ref "U2") (pin "5") (pinfunction "S15_5") (pintype "passive"))
    )
    (net (code "66") (name "unconnected-(U2-S16-Pad4)") (class "Default")
      (node (ref "U2") (pin "4") (pinfunction "S16_4") (pintype "passive"))
    )
  )
)
